# rutten_motor_board.net
KiCad netlist of a schematic drawn in EAGLE
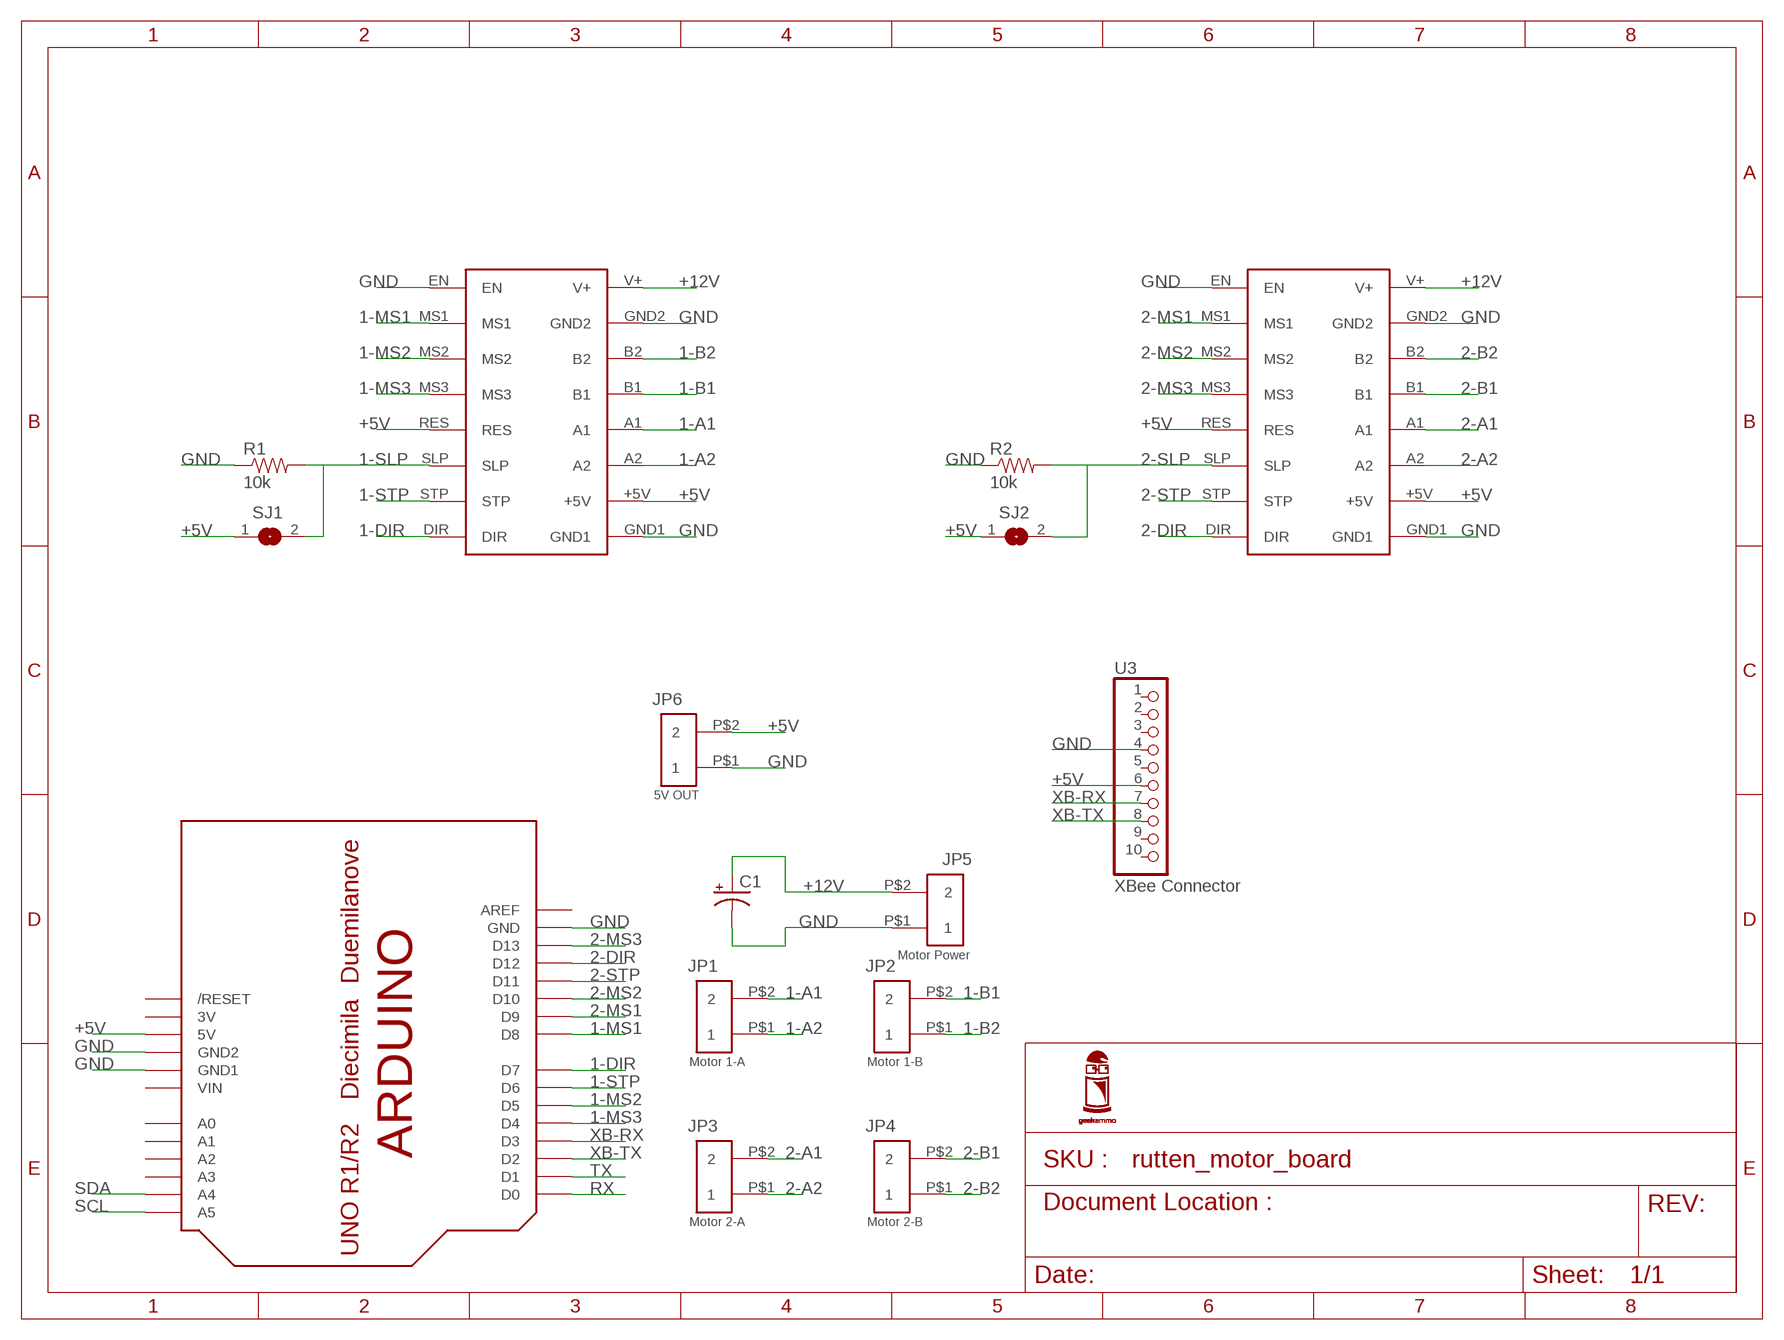
[diagram p0: schematic, sheet 1]

(export (version "E")
  (design (tool "Eeschema 10.0.6"))
  (components
    (comp (ref "C1")
      (value "CAP_POLPTH2")
      (footprint "eagle-import:CPOL-RADIAL-10UF-25V")
      (libsource (lib "eagle-import") (part "CAP_POLPTH2"))
    )
    (comp (ref "JP1")
      (value "Motor 1-A")
      (footprint "eagle-import:SCREW_TERM-200MIL-2")
      (libsource (lib "eagle-import") (part "SCREWTERM-2"))
    )
    (comp (ref "JP2")
      (value "Motor 1-B")
      (footprint "eagle-import:SCREW_TERM-200MIL-2")
      (libsource (lib "eagle-import") (part "SCREWTERM-2"))
    )
    (comp (ref "JP3")
      (value "Motor 2-A")
      (footprint "eagle-import:SCREW_TERM-200MIL-2")
      (libsource (lib "eagle-import") (part "SCREWTERM-2"))
    )
    (comp (ref "JP4")
      (value "Motor 2-B")
      (footprint "eagle-import:SCREW_TERM-200MIL-2")
      (libsource (lib "eagle-import") (part "SCREWTERM-2"))
    )
    (comp (ref "JP5")
      (value "Motor Power")
      (footprint "eagle-import:SCREW_TERM-200MIL-2")
      (libsource (lib "eagle-import") (part "SCREWTERM-2"))
    )
    (comp (ref "JP6")
      (value "5V OUT")
      (footprint "eagle-import:SCREW_TERM-200MIL-2")
      (libsource (lib "eagle-import") (part "SCREWTERM-2"))
    )
    (comp (ref "R1")
      (value "10k")
      (footprint "eagle-import:AXIAL-0.4")
      (libsource (lib "eagle-import") (part "RESISTORPTH-1/4W"))
    )
    (comp (ref "R2")
      (value "10k")
      (footprint "eagle-import:AXIAL-0.4")
      (libsource (lib "eagle-import") (part "RESISTORPTH-1/4W"))
    )
    (comp (ref "SJ1") (value "SJ") (footprint "eagle-import:SJ") (libsource (lib "eagle-import") (part "SJ")))
    (comp (ref "SJ2") (value "SJ") (footprint "eagle-import:SJ") (libsource (lib "eagle-import") (part "SJ")))
    (comp (ref "U$1")
      (value "ARDUINOUNO")
      (footprint "eagle-import:ARDUINO")
      (libsource (lib "eagle-import") (part "ARDUINOUNO"))
    )
    (comp (ref "U1")
      (value "A4988_STEP_STICK")
      (footprint "eagle-import:A9488_STEP_STICK")
      (libsource (lib "eagle-import") (part "A4988_STEP_STICK"))
    )
    (comp (ref "U2")
      (value "A4988_STEP_STICK")
      (footprint "eagle-import:A9488_STEP_STICK")
      (libsource (lib "eagle-import") (part "A4988_STEP_STICK"))
    )
    (comp (ref "U3")
      (value "XBee Connector")
      (footprint "eagle-import:1X10-BIG")
      (libsource (lib "eagle-import") (part "PINHD-1X10"))
    )
  )
  (nets
    (net (code "1") (name "/+5V") (class "Default")
      (node (ref "JP6") (pin "P$2") (pinfunction "2_P$2") (pintype "bidirectional"))
      (node (ref "SJ1") (pin "1") (pinfunction "1_1") (pintype "passive"))
      (node (ref "SJ2") (pin "1") (pinfunction "1_1") (pintype "passive"))
      (node (ref "U$1") (pin "5V") (pinfunction "5V_5V") (pintype "power_in"))
      (node (ref "U1") (pin "+5V") (pinfunction "+5V_+5V") (pintype "power_in"))
      (node (ref "U1") (pin "RES") (pinfunction "RES_RES") (pintype "input"))
      (node (ref "U2") (pin "+5V") (pinfunction "+5V_+5V") (pintype "power_in"))
      (node (ref "U2") (pin "RES") (pinfunction "RES_RES") (pintype "input"))
      (node (ref "U3") (pin "6") (pinfunction "6_6") (pintype "passive"))
    )
    (net (code "2") (name "/+12V") (class "Default")
      (node (ref "C1") (pin "1") (pinfunction "+_1") (pintype "passive"))
      (node (ref "JP5") (pin "P$2") (pinfunction "2_P$2") (pintype "bidirectional"))
      (node (ref "U1") (pin "V+") (pinfunction "V+_V+") (pintype "power_in"))
      (node (ref "U2") (pin "V+") (pinfunction "V+_V+") (pintype "power_in"))
    )
    (net (code "3") (name "/1-A1") (class "Default")
      (node (ref "JP1") (pin "P$2") (pinfunction "2_P$2") (pintype "bidirectional"))
      (node (ref "U1") (pin "A1") (pinfunction "A1_A1") (pintype "output"))
    )
    (net (code "4") (name "/1-A2") (class "Default")
      (node (ref "JP1") (pin "P$1") (pinfunction "1_P$1") (pintype "bidirectional"))
      (node (ref "U1") (pin "A2") (pinfunction "A2_A2") (pintype "output"))
    )
    (net (code "5") (name "/1-B1") (class "Default")
      (node (ref "JP2") (pin "P$2") (pinfunction "2_P$2") (pintype "bidirectional"))
      (node (ref "U1") (pin "B1") (pinfunction "B1_B1") (pintype "output"))
    )
    (net (code "6") (name "/1-B2") (class "Default")
      (node (ref "JP2") (pin "P$1") (pinfunction "1_P$1") (pintype "bidirectional"))
      (node (ref "U1") (pin "B2") (pinfunction "B2_B2") (pintype "output"))
    )
    (net (code "7") (name "/1-DIR") (class "Default")
      (node (ref "U$1") (pin "D7") (pinfunction "D7_D7") (pintype "bidirectional"))
      (node (ref "U1") (pin "DIR") (pinfunction "DIR_DIR") (pintype "input"))
    )
    (net (code "8") (name "/1-MS1") (class "Default")
      (node (ref "U$1") (pin "D8") (pinfunction "D8_D8") (pintype "bidirectional"))
      (node (ref "U1") (pin "MS1") (pinfunction "MS1_MS1") (pintype "input"))
    )
    (net (code "9") (name "/1-MS2") (class "Default")
      (node (ref "U$1") (pin "D5") (pinfunction "D5_D5") (pintype "bidirectional"))
      (node (ref "U1") (pin "MS2") (pinfunction "MS2_MS2") (pintype "input"))
    )
    (net (code "10") (name "/1-MS3") (class "Default")
      (node (ref "U$1") (pin "D4") (pinfunction "D4_D4") (pintype "bidirectional"))
      (node (ref "U1") (pin "MS3") (pinfunction "MS3_MS3") (pintype "input"))
    )
    (net (code "11") (name "/1-SLP") (class "Default")
      (node (ref "R1") (pin "P$2") (pinfunction "2_P$2") (pintype "passive"))
      (node (ref "SJ1") (pin "2") (pinfunction "2_2") (pintype "passive"))
      (node (ref "U1") (pin "SLP") (pinfunction "SLP_SLP") (pintype "input"))
    )
    (net (code "12") (name "/1-STP") (class "Default")
      (node (ref "U$1") (pin "D6") (pinfunction "D6_D6") (pintype "bidirectional"))
      (node (ref "U1") (pin "STP") (pinfunction "STP_STP") (pintype "input"))
    )
    (net (code "13") (name "/2-A1") (class "Default")
      (node (ref "JP3") (pin "P$2") (pinfunction "2_P$2") (pintype "bidirectional"))
      (node (ref "U2") (pin "A1") (pinfunction "A1_A1") (pintype "output"))
    )
    (net (code "14") (name "/2-A2") (class "Default")
      (node (ref "JP3") (pin "P$1") (pinfunction "1_P$1") (pintype "bidirectional"))
      (node (ref "U2") (pin "A2") (pinfunction "A2_A2") (pintype "output"))
    )
    (net (code "15") (name "/2-B1") (class "Default")
      (node (ref "JP4") (pin "P$2") (pinfunction "2_P$2") (pintype "bidirectional"))
      (node (ref "U2") (pin "B1") (pinfunction "B1_B1") (pintype "output"))
    )
    (net (code "16") (name "/2-B2") (class "Default")
      (node (ref "JP4") (pin "P$1") (pinfunction "1_P$1") (pintype "bidirectional"))
      (node (ref "U2") (pin "B2") (pinfunction "B2_B2") (pintype "output"))
    )
    (net (code "17") (name "/2-DIR") (class "Default")
      (node (ref "U$1") (pin "D12") (pinfunction "D12_D12") (pintype "bidirectional"))
      (node (ref "U2") (pin "DIR") (pinfunction "DIR_DIR") (pintype "input"))
    )
    (net (code "18") (name "/2-MS1") (class "Default")
      (node (ref "U$1") (pin "D9") (pinfunction "D9_D9") (pintype "bidirectional"))
      (node (ref "U2") (pin "MS1") (pinfunction "MS1_MS1") (pintype "input"))
    )
    (net (code "19") (name "/2-MS2") (class "Default")
      (node (ref "U$1") (pin "D10") (pinfunction "D10_D10") (pintype "bidirectional"))
      (node (ref "U2") (pin "MS2") (pinfunction "MS2_MS2") (pintype "input"))
    )
    (net (code "20") (name "/2-MS3") (class "Default")
      (node (ref "U$1") (pin "D13") (pinfunction "D13_D13") (pintype "bidirectional"))
      (node (ref "U2") (pin "MS3") (pinfunction "MS3_MS3") (pintype "input"))
    )
    (net (code "21") (name "/2-SLP") (class "Default")
      (node (ref "R2") (pin "P$2") (pinfunction "2_P$2") (pintype "passive"))
      (node (ref "SJ2") (pin "2") (pinfunction "2_2") (pintype "passive"))
      (node (ref "U2") (pin "SLP") (pinfunction "SLP_SLP") (pintype "input"))
    )
    (net (code "22") (name "/2-STP") (class "Default")
      (node (ref "U$1") (pin "D11") (pinfunction "D11_D11") (pintype "bidirectional"))
      (node (ref "U2") (pin "STP") (pinfunction "STP_STP") (pintype "input"))
    )
    (net (code "23") (name "/3V") (class "Default")
      (node (ref "U$1") (pin "3V") (pinfunction "3V_3V") (pintype "power_in"))
    )
    (net (code "24") (name "/GND") (class "Default")
      (node (ref "C1") (pin "2") (pinfunction "-_2") (pintype "passive"))
      (node (ref "JP5") (pin "P$1") (pinfunction "1_P$1") (pintype "bidirectional"))
      (node (ref "JP6") (pin "P$1") (pinfunction "1_P$1") (pintype "bidirectional"))
      (node (ref "R1") (pin "P$1") (pinfunction "1_P$1") (pintype "passive"))
      (node (ref "R2") (pin "P$1") (pinfunction "1_P$1") (pintype "passive"))
      (node (ref "U$1") (pin "GND") (pinfunction "GND_GND") (pintype "power_in"))
      (node (ref "U$1") (pin "GND1") (pinfunction "GND1_GND1") (pintype "power_in"))
      (node (ref "U$1") (pin "GND2") (pinfunction "GND2_GND2") (pintype "power_in"))
      (node (ref "U1") (pin "EN") (pinfunction "EN_EN") (pintype "input"))
      (node (ref "U1") (pin "GND1") (pinfunction "GND1_GND1") (pintype "power_in"))
      (node (ref "U1") (pin "GND2") (pinfunction "GND2_GND2") (pintype "power_in"))
      (node (ref "U2") (pin "EN") (pinfunction "EN_EN") (pintype "input"))
      (node (ref "U2") (pin "GND1") (pinfunction "GND1_GND1") (pintype "power_in"))
      (node (ref "U2") (pin "GND2") (pinfunction "GND2_GND2") (pintype "power_in"))
      (node (ref "U3") (pin "4") (pinfunction "4_4") (pintype "passive"))
    )
    (net (code "25") (name "/RX") (class "Default")
      (node (ref "U$1") (pin "D0") (pinfunction "D0_D0") (pintype "bidirectional"))
    )
    (net (code "26") (name "/SCL") (class "Default")
      (node (ref "U$1") (pin "A5") (pinfunction "A5_A5") (pintype "bidirectional"))
    )
    (net (code "27") (name "/SDA") (class "Default")
      (node (ref "U$1") (pin "A4") (pinfunction "A4_A4") (pintype "bidirectional"))
    )
    (net (code "28") (name "/TX") (class "Default")
      (node (ref "U$1") (pin "D1") (pinfunction "D1_D1") (pintype "bidirectional"))
    )
    (net (code "29") (name "/VIN") (class "Default")
      (node (ref "U$1") (pin "VIN") (pinfunction "VIN_VIN") (pintype "power_in"))
    )
    (net (code "30") (name "/XB-RX") (class "Default")
      (node (ref "U$1") (pin "D3") (pinfunction "D3_D3") (pintype "bidirectional"))
      (node (ref "U3") (pin "7") (pinfunction "7_7") (pintype "passive"))
    )
    (net (code "31") (name "/XB-TX") (class "Default")
      (node (ref "U$1") (pin "D2") (pinfunction "D2_D2") (pintype "bidirectional"))
      (node (ref "U3") (pin "8") (pinfunction "8_8") (pintype "passive"))
    )
    (net (code "32") (name "unconnected-(U$1-PadA0)") (class "Default")
      (node (ref "U$1") (pin "A0") (pinfunction "A0_A0") (pintype "bidirectional"))
    )
    (net (code "33") (name "unconnected-(U$1-PadA1)") (class "Default")
      (node (ref "U$1") (pin "A1") (pinfunction "A1_A1") (pintype "bidirectional"))
    )
    (net (code "34") (name "unconnected-(U$1-PadA2)") (class "Default")
      (node (ref "U$1") (pin "A2") (pinfunction "A2_A2") (pintype "bidirectional"))
    )
    (net (code "35") (name "unconnected-(U$1-PadA3)") (class "Default")
      (node (ref "U$1") (pin "A3") (pinfunction "A3_A3") (pintype "bidirectional"))
    )
    (net (code "36") (name "unconnected-(U$1-PadAREF)") (class "Default")
      (node (ref "U$1") (pin "AREF") (pinfunction "AREF_AREF") (pintype "bidirectional"))
    )
    (net (code "37") (name "unconnected-(U$1-{slash}RESET-PadRESET)") (class "Default")
      (node (ref "U$1") (pin "RESET") (pinfunction "/RESET_RESET") (pintype "bidirectional"))
    )
    (net (code "38") (name "unconnected-(U3-Pad1)") (class "Default")
      (node (ref "U3") (pin "1") (pinfunction "1_1") (pintype "passive"))
    )
    (net (code "39") (name "unconnected-(U3-Pad2)") (class "Default")
      (node (ref "U3") (pin "2") (pinfunction "2_2") (pintype "passive"))
    )
    (net (code "40") (name "unconnected-(U3-Pad3)") (class "Default")
      (node (ref "U3") (pin "3") (pinfunction "3_3") (pintype "passive"))
    )
    (net (code "41") (name "unconnected-(U3-Pad5)") (class "Default")
      (node (ref "U3") (pin "5") (pinfunction "5_5") (pintype "passive"))
    )
    (net (code "42") (name "unconnected-(U3-Pad9)") (class "Default")
      (node (ref "U3") (pin "9") (pinfunction "9_9") (pintype "passive"))
    )
    (net (code "43") (name "unconnected-(U3-Pad10)") (class "Default")
      (node (ref "U3") (pin "10") (pinfunction "10_10") (pintype "passive"))
    )
  )
)
